# 1-Schematic_Pulsera_con_GND.net
KiCad netlist of a schematic drawn in EasyEDA
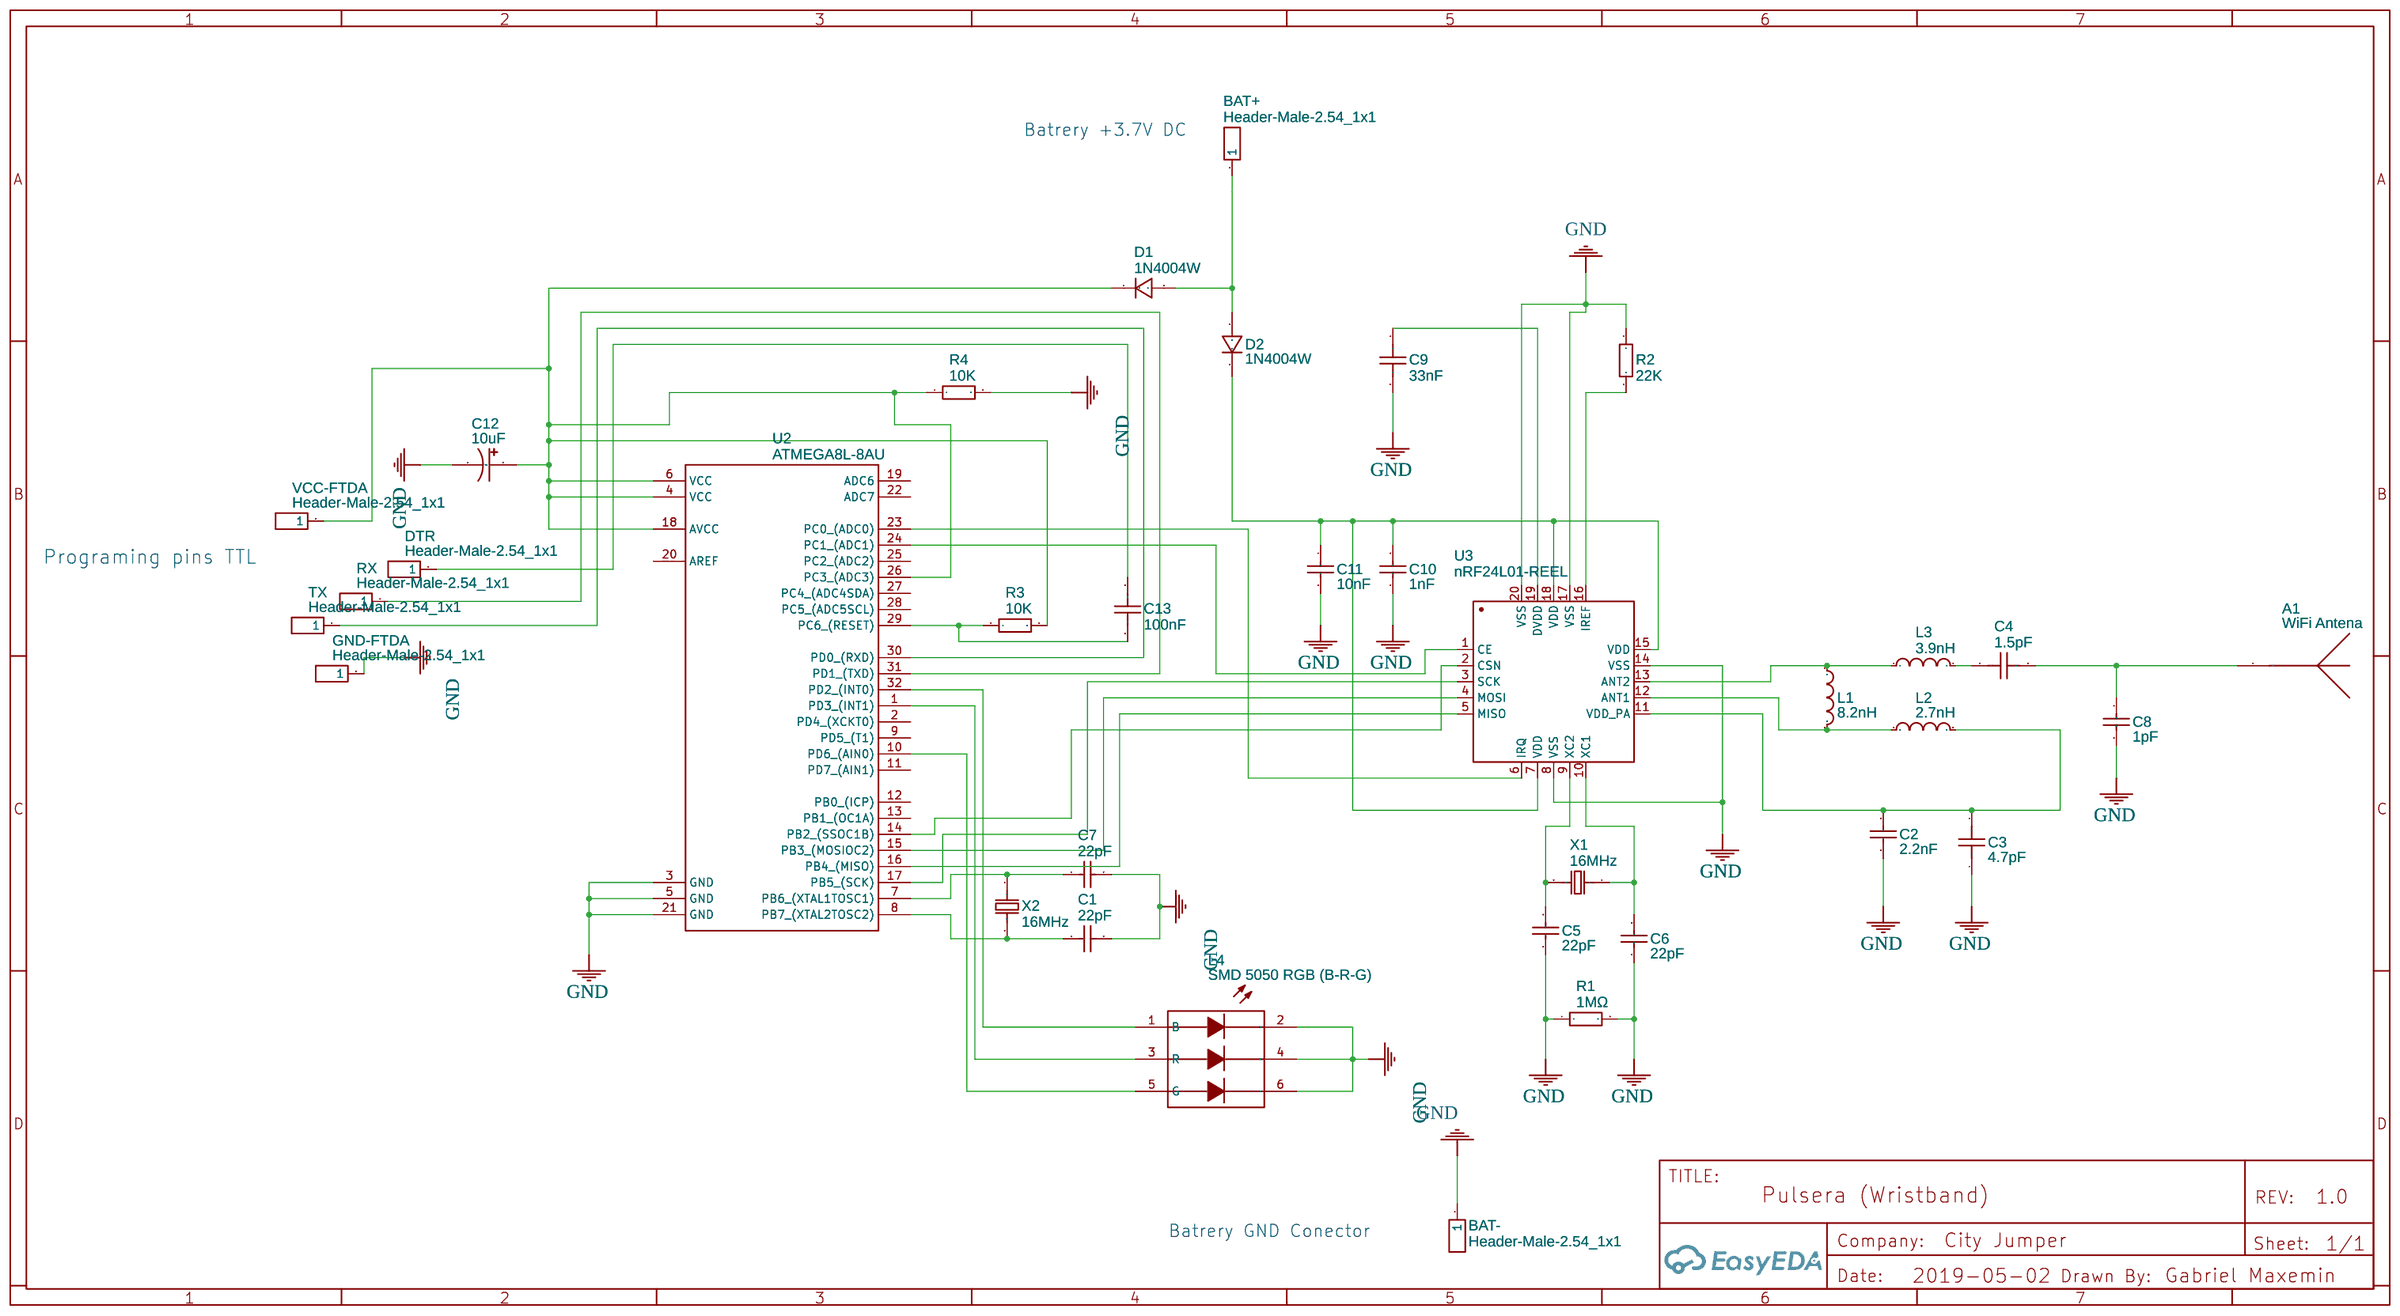
[diagram p0: schematic sheet]

(export (version "E")
  (design (tool "Eeschema 10.0.6"))
  (components
    (comp (ref "A1")
      (value "WiFi Antena")
      (fields (field (name "BOM_Manufacturer Part") "New SchematicLib"))
      (libsource (lib "") (part "Unknown_1430_305"))
    )
    (comp (ref "BAT+")
      (value "Header-Male-2.54_1x1")
      (fields (field (name "BOM_Supplier Part") "C81276"))
      (libsource (lib "") (part "Unknown_760_-15"))
    )
    (comp (ref "BAT-")
      (value "Header-Male-2.54_1x1")
      (fields (field (name "BOM_Supplier Part") "C81276"))
      (libsource (lib "") (part "Unknown_900_655"))
    )
    (comp (ref "C1")
      (value "22pF")
      (fields
        (field (name "BOM_Manufacturer Part") "0402CG220J500NT")
        (field (name "BOM_Supplier Part") "C1555")
      )
      (libsource (lib "") (part "0402CG220J500NT_1"))
    )
    (comp (ref "C2")
      (value "2.2nF")
      (fields
        (field (name "BOM_Manufacturer Part") "0402B222K500NT")
        (field (name "BOM_Supplier Part") "C1531")
      )
      (libsource (lib "") (part "0402B222K500NT"))
    )
    (comp (ref "C3")
      (value "4.7pF")
      (fields
        (field (name "BOM_Manufacturer Part") "GJM1555C1H4R7CB01D")
        (field (name "BOM_Supplier Part") "C85883")
      )
      (libsource (lib "") (part "GJM1555C1H4R7CB01D"))
    )
    (comp (ref "C4")
      (value "1.5pF")
      (fields
        (field (name "BOM_Manufacturer Part") "GJM1555C1H1R5BB01D")
        (field (name "BOM_Supplier Part") "C76900")
      )
      (libsource (lib "") (part "GJM1555C1H1R5BB01D"))
    )
    (comp (ref "C5")
      (value "22pF")
      (fields
        (field (name "BOM_Manufacturer Part") "0402CG220J500NT")
        (field (name "BOM_Supplier Part") "C1555")
      )
      (libsource (lib "") (part "0402CG220J500NT"))
    )
    (comp (ref "C6")
      (value "22pF")
      (fields
        (field (name "BOM_Manufacturer Part") "0402CG220J500NT")
        (field (name "BOM_Supplier Part") "C1555")
      )
      (libsource (lib "") (part "0402CG220J500NT"))
    )
    (comp (ref "C7")
      (value "22pF")
      (fields
        (field (name "BOM_Manufacturer Part") "0402CG220J500NT")
        (field (name "BOM_Supplier Part") "C1555")
      )
      (libsource (lib "") (part "0402CG220J500NT_1"))
    )
    (comp (ref "C8")
      (value "1pF")
      (fields
        (field (name "BOM_Manufacturer Part") "GJM1555C1H1R0BB01D")
        (field (name "BOM_Supplier Part") "C76898")
      )
      (libsource (lib "") (part "GJM1555C1H1R0BB01D"))
    )
    (comp (ref "C9")
      (value "33nF")
      (fields
        (field (name "BOM_Manufacturer Part") "GRM155R71E333KA88D")
        (field (name "BOM_Supplier Part") "C77016")
      )
      (libsource (lib "") (part "GRM155R71E333KA88D"))
    )
    (comp (ref "C10")
      (value "1nF")
      (fields
        (field (name "BOM_Manufacturer Part") "CL05B102KB5NNNC")
        (field (name "BOM_Supplier Part") "C14442")
      )
      (libsource (lib "") (part "CL05B102KB5NNNC"))
    )
    (comp (ref "C11")
      (value "10nF")
      (fields
        (field (name "BOM_Manufacturer Part") "GRM155R71H103KA88D")
        (field (name "BOM_Supplier Part") "C77019")
      )
      (libsource (lib "") (part "GRM155R71H103KA88D"))
    )
    (comp (ref "C12")
      (value "10uF")
      (fields
        (field (name "BOM_Manufacturer Part") "EEE1EA100WR")
        (field (name "BOM_Supplier Part") "C178501")
      )
      (libsource (lib "") (part "EEE1EA100WR"))
    )
    (comp (ref "C13")
      (value "100nF")
      (fields
        (field (name "BOM_Manufacturer Part") "GRM155R61C104KA88D")
        (field (name "BOM_Supplier Part") "C77005")
      )
      (libsource (lib "") (part "GRM155R61C104KA88D"))
    )
    (comp (ref "D1")
      (value "1N4004W")
      (fields (field (name "BOM_Supplier Part") "C162734"))
      (libsource (lib "") (part "Unknown_705_70"))
    )
    (comp (ref "D2")
      (value "1N4004W")
      (fields (field (name "BOM_Supplier Part") "C162734"))
      (libsource (lib "") (part "Unknown_760_105"))
    )
    (comp (ref "DTR")
      (value "Header-Male-2.54_1x1")
      (fields (field (name "BOM_Supplier Part") "C81276"))
      (libsource (lib "") (part "Unknown_250_245"))
    )
    (comp (ref "GND-FTDA")
      (value "Header-Male-2.54_1x1")
      (fields (field (name "BOM_Supplier Part") "C81276"))
      (libsource (lib "") (part "Unknown_205_310"))
    )
    (comp (ref "L1")
      (value "8.2nH")
      (fields
        (field (name "BOM_Manufacturer Part") "SDCL1005C8N2JTDF")
        (field (name "BOM_Supplier Part") "C16208")
      )
      (libsource (lib "") (part "SDCL1005C8N2JTDF"))
    )
    (comp (ref "L2")
      (value "2.7nH")
      (fields
        (field (name "BOM_Manufacturer Part") "SDCL1005C2N7STDF")
        (field (name "BOM_Supplier Part") "C27123")
      )
      (libsource (lib "") (part "SDCL1005C2N7STDF"))
    )
    (comp (ref "L3")
      (value "3.9nH")
      (fields
        (field (name "BOM_Manufacturer Part") "SDCL1005C3N9STDF")
        (field (name "BOM_Supplier Part") "C14033")
      )
      (libsource (lib "") (part "SDCL1005C3N9STDF"))
    )
    (comp (ref "L4")
      (value "SMD 5050 RGB (B-R-G)")
      (fields (field (name "BOM_Manufacturer Part") "SMD 5050 RGB"))
      (libsource (lib "") (part "Unknown_740_520"))
    )
    (comp (ref "R1")
      (value "1MΩ")
      (fields
        (field (name "BOM_Manufacturer Part") "RC0402FR-071ML")
        (field (name "BOM_Supplier Part") "603-RC0402FR-071ML")
      )
      (libsource (lib "") (part "Unknown_980_525"))
    )
    (comp (ref "R2")
      (value "22K")
      (fields
        (field (name "BOM_Manufacturer Part") "0402WGJ0223TCE")
        (field (name "BOM_Supplier Part") "C25547")
      )
      (libsource (lib "") (part "0402WGJ0223TCE"))
    )
    (comp (ref "R3")
      (value "10K")
      (fields
        (field (name "BOM_Manufacturer Part") "0402WGJ0103TCE")
        (field (name "BOM_Supplier Part") "C25531")
      )
      (libsource (lib "") (part "0402WGJ0103TCE"))
    )
    (comp (ref "R4")
      (value "10K")
      (fields
        (field (name "BOM_Manufacturer Part") "0402WGJ0103TCE")
        (field (name "BOM_Supplier Part") "C25531")
      )
      (libsource (lib "") (part "0402WGJ0103TCE"))
    )
    (comp (ref "RX")
      (value "Header-Male-2.54_1x1")
      (fields (field (name "BOM_Supplier Part") "C81276"))
      (libsource (lib "") (part "Unknown_220_265"))
    )
    (comp (ref "TX")
      (value "Header-Male-2.54_1x1")
      (fields (field (name "BOM_Supplier Part") "C81276"))
      (libsource (lib "") (part "Unknown_190_280"))
    )
    (comp (ref "U2")
      (value "ATMEGA8L-8AU")
      (fields (field (name "BOM_Supplier Part") "C9755"))
      (libsource (lib "") (part "Unknown_480_325"))
    )
    (comp (ref "U3")
      (value "nRF24L01-REEL")
      (fields (field (name "BOM_Supplier Part") "C93664"))
      (libsource (lib "") (part "Unknown_960_315"))
    )
    (comp (ref "VCC-FTDA")
      (value "Header-Male-2.54_1x1")
      (fields (field (name "BOM_Supplier Part") "C81276"))
      (libsource (lib "") (part "Unknown_180_215"))
    )
    (comp (ref "X1")
      (value "16MHz")
      (fields
        (field (name "BOM_Manufacturer Part") "X49SSM16MSD2SI")
        (field (name "BOM_Supplier Part") "C96138")
      )
      (libsource (lib "") (part "X49SSM16MSD2SI_1"))
    )
    (comp (ref "X2")
      (value "16MHz")
      (fields
        (field (name "BOM_Manufacturer Part") "X49SSM16MSD2SI")
        (field (name "BOM_Supplier Part") "C96138")
      )
      (libsource (lib "") (part "X49SSM16MSD2SI"))
    )
  )
  (nets
    (net (code "1") (name "GND") (class "Default")
      (node (ref "BAT-") (pin "1") (pinfunction "1_1") (pintype "input"))
      (node (ref "C1") (pin "2") (pinfunction "2_2") (pintype "input"))
      (node (ref "C10") (pin "1") (pinfunction "1_1") (pintype "input"))
      (node (ref "C11") (pin "2") (pinfunction "2_2") (pintype "input"))
      (node (ref "C12") (pin "2") (pinfunction "2_2") (pintype "unspecified"))
      (node (ref "C2") (pin "1") (pinfunction "1_1") (pintype "input"))
      (node (ref "C3") (pin "1") (pinfunction "1_1") (pintype "unspecified"))
      (node (ref "C5") (pin "1") (pinfunction "1_1") (pintype "input"))
      (node (ref "C6") (pin "1") (pinfunction "1_1") (pintype "input"))
      (node (ref "C7") (pin "2") (pinfunction "2_2") (pintype "input"))
      (node (ref "C8") (pin "2") (pinfunction "2_2") (pintype "input"))
      (node (ref "C9") (pin "2") (pinfunction "2_2") (pintype "unspecified"))
      (node (ref "GND-FTDA") (pin "1") (pinfunction "1_1") (pintype "input"))
      (node (ref "L4") (pin "2") (pinfunction "B-_2") (pintype "unspecified"))
      (node (ref "L4") (pin "4") (pinfunction "R-_4") (pintype "unspecified"))
      (node (ref "L4") (pin "6") (pinfunction "-g_6") (pintype "unspecified"))
      (node (ref "R1") (pin "1") (pinfunction "1_1") (pintype "input"))
      (node (ref "R1") (pin "2") (pinfunction "2_2") (pintype "input"))
      (node (ref "R2") (pin "2") (pinfunction "2_2") (pintype "input"))
      (node (ref "R4") (pin "2") (pinfunction "2_2") (pintype "input"))
      (node (ref "U2") (pin "21") (pinfunction "GND_21") (pintype "passive"))
      (node (ref "U2") (pin "3") (pinfunction "GND_3") (pintype "passive"))
      (node (ref "U2") (pin "5") (pinfunction "GND_5") (pintype "passive"))
      (node (ref "U3") (pin "14") (pinfunction "VSS_14") (pintype "unspecified"))
      (node (ref "U3") (pin "17") (pinfunction "VSS_17") (pintype "unspecified"))
      (node (ref "U3") (pin "20") (pinfunction "VSS_20") (pintype "unspecified"))
      (node (ref "U3") (pin "8") (pinfunction "VSS_8") (pintype "unspecified"))
    )
    (net (code "2") (name "Net-(A1-Pad1)") (class "Default")
      (node (ref "A1") (pin "1") (pinfunction "1_1") (pintype "output"))
      (node (ref "C4") (pin "2") (pinfunction "2_2") (pintype "unspecified"))
      (node (ref "C8") (pin "1") (pinfunction "1_1") (pintype "input"))
    )
    (net (code "3") (name "Net-(BAT+-Pad1)") (class "Default")
      (node (ref "BAT+") (pin "1") (pinfunction "1_1") (pintype "input"))
      (node (ref "D1") (pin "2") (pinfunction "2_2") (pintype "unspecified"))
      (node (ref "D2") (pin "2") (pinfunction "2_2") (pintype "unspecified"))
    )
    (net (code "4") (name "Net-(C4-Pad1)") (class "Default")
      (node (ref "C4") (pin "1") (pinfunction "1_1") (pintype "unspecified"))
      (node (ref "L3") (pin "2") (pinfunction "2_2") (pintype "unspecified"))
    )
    (net (code "5") (name "Net-(C10-Pad2)") (class "Default")
      (node (ref "C10") (pin "2") (pinfunction "2_2") (pintype "input"))
      (node (ref "C11") (pin "1") (pinfunction "1_1") (pintype "input"))
      (node (ref "D2") (pin "1") (pinfunction "1_1") (pintype "unspecified"))
      (node (ref "U3") (pin "15") (pinfunction "VDD_15") (pintype "unspecified"))
      (node (ref "U3") (pin "18") (pinfunction "VDD_18") (pintype "unspecified"))
      (node (ref "U3") (pin "7") (pinfunction "VDD_7") (pintype "unspecified"))
    )
    (net (code "6") (name "Net-(C13-Pad2)") (class "Default")
      (node (ref "C13") (pin "2") (pinfunction "2_2") (pintype "unspecified"))
      (node (ref "DTR") (pin "1") (pinfunction "1_1") (pintype "input"))
    )
    (net (code "7") (name "Net-(L4-B)") (class "Default")
      (node (ref "L4") (pin "1") (pinfunction "B_1") (pintype "unspecified"))
      (node (ref "U2") (pin "32") (pinfunction "PD2_(INT0)_32") (pintype "bidirectional"))
    )
    (net (code "8") (name "Net-(L4-G)") (class "Default")
      (node (ref "L4") (pin "5") (pinfunction "G_5") (pintype "unspecified"))
      (node (ref "U2") (pin "10") (pinfunction "PD6_(AIN0)_10") (pintype "bidirectional"))
    )
    (net (code "9") (name "Net-(L4-R)") (class "Default")
      (node (ref "L4") (pin "3") (pinfunction "R_3") (pintype "unspecified"))
      (node (ref "U2") (pin "1") (pinfunction "PD3_(INT1)_1") (pintype "bidirectional"))
    )
    (net (code "10") (name "Net-(U2-AVCC)") (class "Default")
      (node (ref "C12") (pin "1") (pinfunction "1_1") (pintype "unspecified"))
      (node (ref "D1") (pin "1") (pinfunction "1_1") (pintype "unspecified"))
      (node (ref "R3") (pin "2") (pinfunction "2_2") (pintype "input"))
      (node (ref "R4") (pin "1") (pinfunction "1_1") (pintype "input"))
      (node (ref "U2") (pin "18") (pinfunction "AVCC_18") (pintype "passive"))
      (node (ref "U2") (pin "26") (pinfunction "PC3_(ADC3)_26") (pintype "bidirectional"))
      (node (ref "U2") (pin "4") (pinfunction "VCC_4") (pintype "passive"))
      (node (ref "U2") (pin "6") (pinfunction "VCC_6") (pintype "passive"))
      (node (ref "VCC-FTDA") (pin "1") (pinfunction "1_1") (pintype "input"))
    )
    (net (code "11") (name "Net-(U2-PB2_(SSOC1B))") (class "Default")
      (node (ref "U2") (pin "14") (pinfunction "PB2_(SSOC1B)_14") (pintype "bidirectional"))
      (node (ref "U3") (pin "2") (pinfunction "CSN_2") (pintype "unspecified"))
    )
    (net (code "12") (name "Net-(U2-PB3_(MOSIOC2))") (class "Default")
      (node (ref "U2") (pin "15") (pinfunction "PB3_(MOSIOC2)_15") (pintype "bidirectional"))
      (node (ref "U3") (pin "4") (pinfunction "MOSI_4") (pintype "unspecified"))
    )
    (net (code "13") (name "Net-(U2-PB4_(MISO))") (class "Default")
      (node (ref "U2") (pin "16") (pinfunction "PB4_(MISO)_16") (pintype "bidirectional"))
      (node (ref "U3") (pin "5") (pinfunction "MISO_5") (pintype "unspecified"))
    )
    (net (code "14") (name "Net-(U2-PB5_(SCK))") (class "Default")
      (node (ref "U2") (pin "17") (pinfunction "PB5_(SCK)_17") (pintype "bidirectional"))
      (node (ref "U3") (pin "3") (pinfunction "SCK_3") (pintype "unspecified"))
    )
    (net (code "15") (name "Net-(U2-PB6_(XTAL1TOSC1))") (class "Default")
      (node (ref "C7") (pin "1") (pinfunction "1_1") (pintype "input"))
      (node (ref "U2") (pin "7") (pinfunction "PB6_(XTAL1TOSC1)_7") (pintype "bidirectional"))
      (node (ref "X2") (pin "1") (pinfunction "1_1") (pintype "unspecified"))
    )
    (net (code "16") (name "Net-(U2-PB7_(XTAL2TOSC2))") (class "Default")
      (node (ref "C1") (pin "1") (pinfunction "1_1") (pintype "input"))
      (node (ref "U2") (pin "8") (pinfunction "PB7_(XTAL2TOSC2)_8") (pintype "bidirectional"))
      (node (ref "X2") (pin "2") (pinfunction "2_2") (pintype "unspecified"))
    )
    (net (code "17") (name "Net-(U2-PC0_(ADC0))") (class "Default")
      (node (ref "U2") (pin "23") (pinfunction "PC0_(ADC0)_23") (pintype "bidirectional"))
      (node (ref "U3") (pin "6") (pinfunction "IRQ_6") (pintype "unspecified"))
    )
    (net (code "18") (name "Net-(U2-PC1_(ADC1))") (class "Default")
      (node (ref "U2") (pin "24") (pinfunction "PC1_(ADC1)_24") (pintype "bidirectional"))
      (node (ref "U3") (pin "1") (pinfunction "CE_1") (pintype "unspecified"))
    )
    (net (code "19") (name "Net-(U2-PC6_(RESET))") (class "Default")
      (node (ref "C13") (pin "1") (pinfunction "1_1") (pintype "unspecified"))
      (node (ref "R3") (pin "1") (pinfunction "1_1") (pintype "input"))
      (node (ref "U2") (pin "29") (pinfunction "PC6_(RESET)_29") (pintype "bidirectional"))
    )
    (net (code "20") (name "Net-(U2-PD0_(RXD))") (class "Default")
      (node (ref "TX") (pin "1") (pinfunction "1_1") (pintype "input"))
      (node (ref "U2") (pin "30") (pinfunction "PD0_(RXD)_30") (pintype "bidirectional"))
    )
    (net (code "21") (name "Net-(U2-PD1_(TXD))") (class "Default")
      (node (ref "RX") (pin "1") (pinfunction "1_1") (pintype "input"))
      (node (ref "U2") (pin "31") (pinfunction "PD1_(TXD)_31") (pintype "bidirectional"))
    )
    (net (code "22") (name "Net-(U3-ANT1)") (class "Default")
      (node (ref "L1") (pin "2") (pinfunction "2_2") (pintype "unspecified"))
      (node (ref "L2") (pin "1") (pinfunction "1_1") (pintype "unspecified"))
      (node (ref "U3") (pin "12") (pinfunction "ANT1_12") (pintype "unspecified"))
    )
    (net (code "23") (name "Net-(U3-ANT2)") (class "Default")
      (node (ref "L1") (pin "1") (pinfunction "1_1") (pintype "unspecified"))
      (node (ref "L3") (pin "1") (pinfunction "1_1") (pintype "unspecified"))
      (node (ref "U3") (pin "13") (pinfunction "ANT2_13") (pintype "unspecified"))
    )
    (net (code "24") (name "Net-(U3-DVDD)") (class "Default")
      (node (ref "C9") (pin "1") (pinfunction "1_1") (pintype "unspecified"))
      (node (ref "U3") (pin "19") (pinfunction "DVDD_19") (pintype "unspecified"))
    )
    (net (code "25") (name "Net-(U3-IREF)") (class "Default")
      (node (ref "R2") (pin "1") (pinfunction "1_1") (pintype "input"))
      (node (ref "U3") (pin "16") (pinfunction "IREF_16") (pintype "unspecified"))
    )
    (net (code "26") (name "Net-(U3-VDD_PA)") (class "Default")
      (node (ref "C2") (pin "2") (pinfunction "2_2") (pintype "input"))
      (node (ref "C3") (pin "2") (pinfunction "2_2") (pintype "unspecified"))
      (node (ref "L2") (pin "2") (pinfunction "2_2") (pintype "unspecified"))
      (node (ref "U3") (pin "11") (pinfunction "VDD_PA_11") (pintype "unspecified"))
    )
    (net (code "27") (name "Net-(U3-XC1)") (class "Default")
      (node (ref "C6") (pin "2") (pinfunction "2_2") (pintype "input"))
      (node (ref "U3") (pin "10") (pinfunction "XC1_10") (pintype "unspecified"))
      (node (ref "X1") (pin "1") (pinfunction "1_1") (pintype "unspecified"))
    )
    (net (code "28") (name "Net-(U3-XC2)") (class "Default")
      (node (ref "C5") (pin "2") (pinfunction "2_2") (pintype "input"))
      (node (ref "U3") (pin "9") (pinfunction "XC2_9") (pintype "unspecified"))
      (node (ref "X1") (pin "2") (pinfunction "2_2") (pintype "unspecified"))
    )
    (net (code "29") (name "unconnected-(U2-ADC6-Pad19)") (class "Default")
      (node (ref "U2") (pin "19") (pinfunction "ADC6_19") (pintype "unspecified"))
    )
    (net (code "30") (name "unconnected-(U2-ADC7-Pad22)") (class "Default")
      (node (ref "U2") (pin "22") (pinfunction "ADC7_22") (pintype "unspecified"))
    )
    (net (code "31") (name "unconnected-(U2-AREF-Pad20)") (class "Default")
      (node (ref "U2") (pin "20") (pinfunction "AREF_20") (pintype "unspecified"))
    )
    (net (code "32") (name "unconnected-(U2-PB0_(ICP)-Pad12)") (class "Default")
      (node (ref "U2") (pin "12") (pinfunction "PB0_(ICP)_12") (pintype "bidirectional"))
    )
    (net (code "33") (name "unconnected-(U2-PB1_(OC1A)-Pad13)") (class "Default")
      (node (ref "U2") (pin "13") (pinfunction "PB1_(OC1A)_13") (pintype "bidirectional"))
    )
    (net (code "34") (name "unconnected-(U2-PC2_(ADC2)-Pad25)") (class "Default")
      (node (ref "U2") (pin "25") (pinfunction "PC2_(ADC2)_25") (pintype "bidirectional"))
    )
    (net (code "35") (name "unconnected-(U2-PC4_(ADC4SDA)-Pad27)") (class "Default")
      (node (ref "U2") (pin "27") (pinfunction "PC4_(ADC4SDA)_27") (pintype "bidirectional"))
    )
    (net (code "36") (name "unconnected-(U2-PC5_(ADC5SCL)-Pad28)") (class "Default")
      (node (ref "U2") (pin "28") (pinfunction "PC5_(ADC5SCL)_28") (pintype "bidirectional"))
    )
    (net (code "37") (name "unconnected-(U2-PD4_(XCKT0)-Pad2)") (class "Default")
      (node (ref "U2") (pin "2") (pinfunction "PD4_(XCKT0)_2") (pintype "bidirectional"))
    )
    (net (code "38") (name "unconnected-(U2-PD5_(T1)-Pad9)") (class "Default")
      (node (ref "U2") (pin "9") (pinfunction "PD5_(T1)_9") (pintype "bidirectional"))
    )
    (net (code "39") (name "unconnected-(U2-PD7_(AIN1)-Pad11)") (class "Default")
      (node (ref "U2") (pin "11") (pinfunction "PD7_(AIN1)_11") (pintype "bidirectional"))
    )
  )
)
